# LDO_3V3.net
KiCad netlist of a schematic drawn in Altium Designer
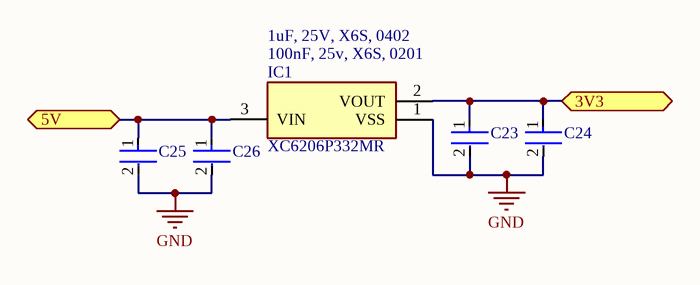
[diagram p0: LDO_3V3.SchDoc]

(export (version "E")
  (design (tool "Eeschema 10.0.6"))
  (components
    (comp (ref "C23")
      (value "100nF, 25v, X6S, 0201")
      (footprint "FP-GRM033-0_03-IPC_B")
      (description "Chip Multilayer Ceramic Capacitors for General Purpose, 0201, 0.10uF, X6S, 22%, 10%, 25V")
      (fields (field (name "TOLERANCE") "10%"))
      (libsource (lib "Altium Content Vault") (part "b4654b650e69147ec39a6b967a45e02"))
    )
    (comp (ref "C24")
      (value "1uF, 25V, X6S, 0402")
      (footprint "FP-GRT155-0_1-IPC_A")
      (description "Multi-Layer Ceramic Capacitor 1uF 25V X6S ±10% 0402 Paper T/R")
      (libsource (lib "Altium Content Vault") (part "02cd4be3c70576c341d710602a673aa"))
    )
    (comp (ref "C25")
      (value "1uF, 25V, X6S, 0402")
      (footprint "FP-GRT155-0_1-IPC_A")
      (description "Multi-Layer Ceramic Capacitor 1uF 25V X6S ±10% 0402 Paper T/R")
      (libsource (lib "Altium Content Vault") (part "02cd4be3c70576c341d710602a673aa"))
    )
    (comp (ref "C26")
      (value "100nF, 25v, X6S, 0201")
      (footprint "FP-GRM033-0_03-IPC_B")
      (description "Chip Multilayer Ceramic Capacitors for General Purpose, 0201, 0.10uF, X6S, 22%, 10%, 25V")
      (fields (field (name "TOLERANCE") "10%"))
      (libsource (lib "Altium Content Vault") (part "b4654b650e69147ec39a6b967a45e02"))
    )
    (comp (ref "IC1")
      (value "XC6206P332MR")
      (footprint "SamacSys:SOT95P280X130-3N")
      (description "Integrated Circuit")
      (libsource (lib "*") (part "XC6206P332MR"))
    )
  )
  (nets
    (net (code "1") (name "/3V3") (class "Default")
      (node (ref "C23") (pin "1") (pinfunction "1_1") (pintype "passive"))
      (node (ref "C24") (pin "1") (pinfunction "1_1") (pintype "passive"))
      (node (ref "IC1") (pin "2") (pinfunction "VOUT_2") (pintype "passive"))
    )
    (net (code "2") (name "/5V") (class "Default")
      (node (ref "C25") (pin "1") (pinfunction "1_1") (pintype "passive"))
      (node (ref "C26") (pin "1") (pinfunction "1_1") (pintype "passive"))
      (node (ref "IC1") (pin "3") (pinfunction "VIN_3") (pintype "passive"))
    )
    (net (code "3") (name "GND") (class "Default")
      (node (ref "C23") (pin "2") (pinfunction "2_2") (pintype "passive"))
      (node (ref "C24") (pin "2") (pinfunction "2_2") (pintype "passive"))
      (node (ref "C25") (pin "2") (pinfunction "2_2") (pintype "passive"))
      (node (ref "C26") (pin "2") (pinfunction "2_2") (pintype "passive"))
      (node (ref "IC1") (pin "1") (pinfunction "VSS_1") (pintype "passive"))
    )
  )
)
